# v3.net
KiCad netlist of a schematic drawn in EAGLE
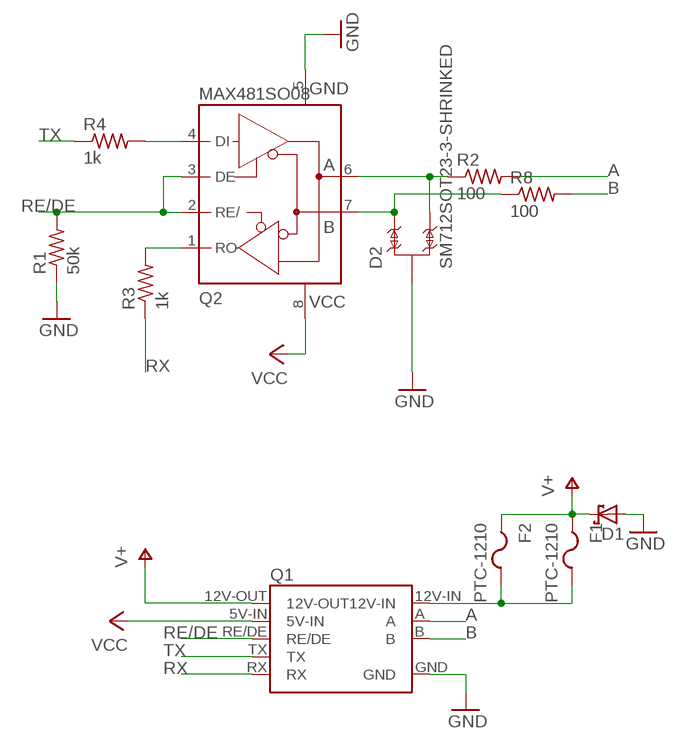
[diagram p0: schematic, sheet 1]

(export (version "E")
  (design (tool "Eeschema 10.0.6"))
  (components
    (comp (ref "D1")
      (value "SCHOTTKY-DIODESMC")
      (footprint "eagle-import:SMC")
      (libsource (lib "eagle-import") (part "SCHOTTKY-DIODESMC"))
    )
    (comp (ref "D2")
      (value "SM712SOT23-3-SHRINKED")
      (footprint "eagle-import:SOT23-3-SHRINKED")
      (libsource (lib "eagle-import") (part "SM712SOT23-3-SHRINKED"))
    )
    (comp (ref "F1")
      (value "PTC-1210")
      (footprint "eagle-import:1210")
      (libsource (lib "eagle-import") (part "PTC-1210"))
    )
    (comp (ref "F2")
      (value "PTC-1210")
      (footprint "eagle-import:1210")
      (libsource (lib "eagle-import") (part "PTC-1210"))
    )
    (comp (ref "Q1")
      (value "RS485-ADAPTER0.05-CONNECTOR")
      (footprint "eagle-import:RS485-ADAPTOR-05")
      (libsource (lib "eagle-import") (part "RS485-ADAPTER0.05-CONNECTOR"))
    )
    (comp (ref "Q2")
      (value "MAX481SO08")
      (footprint "eagle-import:SO08")
      (libsource (lib "eagle-import") (part "MAX481SO08"))
    )
    (comp (ref "R1")
      (value "50k")
      (footprint "eagle-import:R0603")
      (libsource (lib "eagle-import") (part "R-US_R0603"))
    )
    (comp (ref "R2")
      (value "100")
      (footprint "eagle-import:R0603")
      (libsource (lib "eagle-import") (part "R-US_R0603"))
    )
    (comp (ref "R3")
      (value "1k")
      (footprint "eagle-import:R0603")
      (libsource (lib "eagle-import") (part "R-US_R0603"))
    )
    (comp (ref "R4")
      (value "1k")
      (footprint "eagle-import:R0603")
      (libsource (lib "eagle-import") (part "R-US_R0603"))
    )
    (comp (ref "R8")
      (value "100")
      (footprint "eagle-import:R0603")
      (libsource (lib "eagle-import") (part "R-US_R0603"))
    )
  )
  (nets
    (net (code "1") (name "/A") (class "Default")
      (node (ref "Q1") (pin "A") (pinfunction "A_A") (pintype "bidirectional"))
      (node (ref "R2") (pin "2") (pinfunction "2_2") (pintype "passive"))
    )
    (net (code "2") (name "/B") (class "Default")
      (node (ref "Q1") (pin "B") (pinfunction "B_B") (pintype "bidirectional"))
      (node (ref "R8") (pin "2") (pinfunction "2_2") (pintype "passive"))
    )
    (net (code "3") (name "/RE{slash}DE") (class "Default")
      (node (ref "Q1") (pin "RE/DE") (pinfunction "RE/DE_RE/DE") (pintype "bidirectional"))
      (node (ref "Q2") (pin "2") (pinfunction "RE/_2") (pintype "input"))
      (node (ref "Q2") (pin "3") (pinfunction "DE_3") (pintype "input"))
      (node (ref "R1") (pin "2") (pinfunction "2_2") (pintype "passive"))
    )
    (net (code "4") (name "/RX") (class "Default")
      (node (ref "Q1") (pin "RX") (pinfunction "RX_RX") (pintype "bidirectional"))
      (node (ref "R3") (pin "1") (pinfunction "1_1") (pintype "passive"))
    )
    (net (code "5") (name "/TX") (class "Default")
      (node (ref "Q1") (pin "TX") (pinfunction "TX_TX") (pintype "bidirectional"))
      (node (ref "R4") (pin "1") (pinfunction "1_1") (pintype "passive"))
    )
    (net (code "6") (name "GND") (class "Default")
      (node (ref "D1") (pin "A") (pinfunction "A_A") (pintype "passive"))
      (node (ref "D2") (pin "3") (pinfunction "3_3") (pintype "passive"))
      (node (ref "Q1") (pin "GND") (pinfunction "GND_GND") (pintype "power_in"))
      (node (ref "Q2") (pin "5") (pinfunction "GND_5") (pintype "power_in"))
      (node (ref "R1") (pin "1") (pinfunction "1_1") (pintype "passive"))
    )
    (net (code "7") (name "Net-(F1-Pad2)") (class "Default")
      (node (ref "F1") (pin "2") (pinfunction "2_2") (pintype "passive"))
      (node (ref "F2") (pin "2") (pinfunction "2_2") (pintype "passive"))
      (node (ref "Q1") (pin "12V-IN") (pinfunction "12V-IN_12V-IN") (pintype "power_in"))
    )
    (net (code "8") (name "Net-(Q2-A)") (class "Default")
      (node (ref "D2") (pin "1") (pinfunction "1_1") (pintype "passive"))
      (node (ref "Q2") (pin "6") (pinfunction "A_6") (pintype "passive"))
      (node (ref "R2") (pin "1") (pinfunction "1_1") (pintype "passive"))
    )
    (net (code "9") (name "Net-(Q2-B)") (class "Default")
      (node (ref "D2") (pin "2") (pinfunction "2_2") (pintype "passive"))
      (node (ref "Q2") (pin "7") (pinfunction "B_7") (pintype "passive"))
      (node (ref "R8") (pin "1") (pinfunction "1_1") (pintype "passive"))
    )
    (net (code "10") (name "Net-(Q2-DI)") (class "Default")
      (node (ref "Q2") (pin "4") (pinfunction "DI_4") (pintype "input"))
      (node (ref "R4") (pin "2") (pinfunction "2_2") (pintype "passive"))
    )
    (net (code "11") (name "Net-(Q2-RO)") (class "Default")
      (node (ref "Q2") (pin "1") (pinfunction "RO_1") (pintype "output"))
      (node (ref "R3") (pin "2") (pinfunction "2_2") (pintype "passive"))
    )
    (net (code "12") (name "V+") (class "Default")
      (node (ref "D1") (pin "C") (pinfunction "C_C") (pintype "passive"))
      (node (ref "F1") (pin "1") (pinfunction "1_1") (pintype "passive"))
      (node (ref "F2") (pin "1") (pinfunction "1_1") (pintype "passive"))
      (node (ref "Q1") (pin "12V-OUT") (pinfunction "12V-OUT_12V-OUT") (pintype "power_in"))
    )
    (net (code "13") (name "VCC") (class "Default")
      (node (ref "Q1") (pin "5V-IN") (pinfunction "5V-IN_5V-IN") (pintype "power_in"))
      (node (ref "Q2") (pin "8") (pinfunction "+5V_8") (pintype "power_in"))
    )
  )
)
